# ME433_Breakout.net
KiCad netlist of a schematic drawn in EAGLE
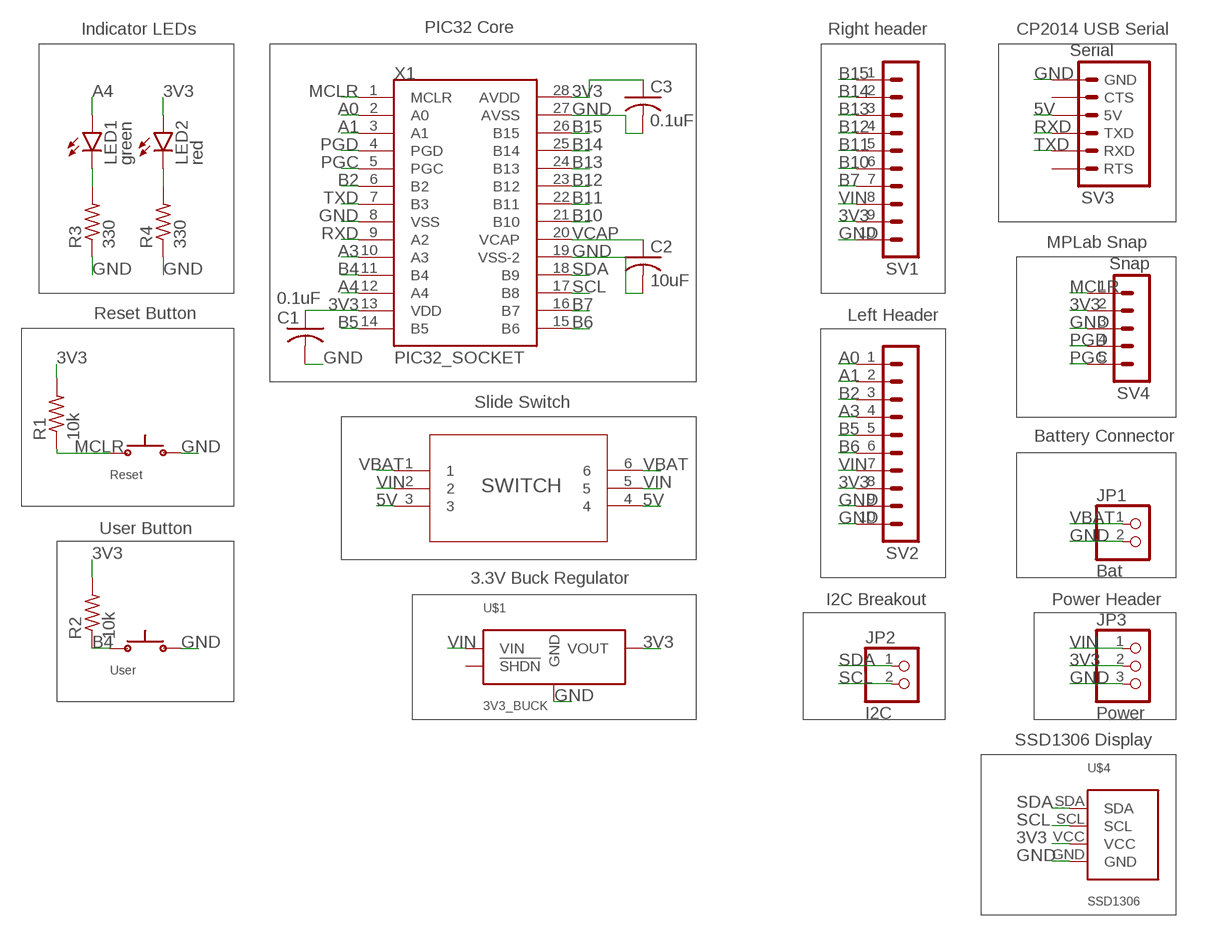
[diagram p0: schematic, sheet 1]

(export (version "E")
  (design (tool "Eeschema 10.0.6"))
  (components
    (comp (ref "C1")
      (value "0.1uF")
      (footprint "eagle-import:C025-025X050")
      (libsource (lib "eagle-import") (part "C-US025-025X050"))
    )
    (comp (ref "C2")
      (value "10uF")
      (footprint "eagle-import:C025-025X050")
      (libsource (lib "eagle-import") (part "C-US025-025X050"))
    )
    (comp (ref "C3")
      (value "0.1uF")
      (footprint "eagle-import:C025-025X050")
      (libsource (lib "eagle-import") (part "C-US025-025X050"))
    )
    (comp (ref "JP1")
      (value "Bat")
      (footprint "eagle-import:1X02")
      (libsource (lib "eagle-import") (part "PINHD-1X2"))
    )
    (comp (ref "JP2")
      (value "I2C")
      (footprint "eagle-import:1X02")
      (libsource (lib "eagle-import") (part "PINHD-1X2"))
    )
    (comp (ref "JP3")
      (value "Power")
      (footprint "eagle-import:1X03")
      (libsource (lib "eagle-import") (part "PINHD-1X3"))
    )
    (comp (ref "LED1")
      (value "green")
      (footprint "eagle-import:LED3MM")
      (libsource (lib "eagle-import") (part "LED3MM"))
    )
    (comp (ref "LED2")
      (value "red")
      (footprint "eagle-import:LED3MM")
      (libsource (lib "eagle-import") (part "LED3MM"))
    )
    (comp (ref "R1")
      (value "10k")
      (footprint "eagle-import:0207_10")
      (libsource (lib "eagle-import") (part "R-US_0207/10"))
    )
    (comp (ref "R2")
      (value "10k")
      (footprint "eagle-import:0207_10")
      (libsource (lib "eagle-import") (part "R-US_0207/10"))
    )
    (comp (ref "R3")
      (value "330")
      (footprint "eagle-import:0207_10")
      (libsource (lib "eagle-import") (part "R-US_0207/10"))
    )
    (comp (ref "R4")
      (value "330")
      (footprint "eagle-import:0207_10")
      (libsource (lib "eagle-import") (part "R-US_0207/10"))
    )
    (comp (ref "SV1")
      (value "MA10-1")
      (footprint "eagle-import:MA10-1")
      (libsource (lib "eagle-import") (part "MA10-1"))
    )
    (comp (ref "SV2")
      (value "MA10-1")
      (footprint "eagle-import:MA10-1")
      (libsource (lib "eagle-import") (part "MA10-1"))
    )
    (comp (ref "SV3")
      (value "Serial")
      (footprint "eagle-import:MA06-1")
      (libsource (lib "eagle-import") (part "CP2014_BREAKOUT"))
    )
    (comp (ref "SV4")
      (value "Snap")
      (footprint "eagle-import:MA05-1")
      (libsource (lib "eagle-import") (part "MA05-1"))
    )
    (comp (ref "U$1")
      (value "3V3_BUCK")
      (footprint "eagle-import:3V3_BUCK")
      (libsource (lib "eagle-import") (part "3V3_BUCK"))
    )
    (comp (ref "U$2")
      (value "Reset")
      (footprint "eagle-import:PUSH_BUTTON")
      (libsource (lib "eagle-import") (part "PUSH_BUTTON"))
    )
    (comp (ref "U$3")
      (value "User")
      (footprint "eagle-import:PUSH_BUTTON")
      (libsource (lib "eagle-import") (part "PUSH_BUTTON"))
    )
    (comp (ref "U$4")
      (value "SSD1306")
      (footprint "eagle-import:SSD1306")
      (libsource (lib "eagle-import") (part "SSD1306"))
    )
    (comp (ref "U1")
      (value "SWITCH")
      (footprint "eagle-import:SWITCH_011CQN")
      (fields
        (field (name "MANUFACTURER_PART_NUMBER") "JS202011CQN")
        (field (name "COPYRIGHT") "Copyright (C) 2022 Ultra Librarian. All rights reserved.")
      )
      (libsource (lib "eagle-import") (part "SWITCH"))
    )
    (comp (ref "X1")
      (value "PIC32_SOCKET")
      (footprint "eagle-import:OST_ED281DT")
      (fields
        (field (name "DIGI-KEY_PART_NUMBER") "ED3050-5-ND")
        (field (name "MF") "On Shore")
        (field (name "MP") "ED281DT")
      )
      (libsource (lib "eagle-import") (part "PIC32_SOCKET"))
    )
  )
  (nets
    (net (code "1") (name "/3V3") (class "Default")
      (node (ref "C1") (pin "1") (pinfunction "1_1") (pintype "passive"))
      (node (ref "C3") (pin "1") (pinfunction "1_1") (pintype "passive"))
      (node (ref "JP3") (pin "2") (pinfunction "2_2") (pintype "passive"))
      (node (ref "LED2") (pin "A") (pinfunction "A_A") (pintype "passive"))
      (node (ref "R1") (pin "2") (pinfunction "2_2") (pintype "passive"))
      (node (ref "R2") (pin "2") (pinfunction "2_2") (pintype "passive"))
      (node (ref "SV1") (pin "9") (pinfunction "9_9") (pintype "passive"))
      (node (ref "SV2") (pin "8") (pinfunction "8_8") (pintype "passive"))
      (node (ref "SV4") (pin "2") (pinfunction "2_2") (pintype "passive"))
      (node (ref "U$1") (pin "VOUT") (pinfunction "VOUT_VOUT") (pintype "bidirectional"))
      (node (ref "U$4") (pin "VCC") (pinfunction "VCC_VCC") (pintype "passive"))
      (node (ref "X1") (pin "13") (pinfunction "VDD_13") (pintype "passive"))
      (node (ref "X1") (pin "28") (pinfunction "AVDD_28") (pintype "passive"))
    )
    (net (code "2") (name "/5V") (class "Default")
      (node (ref "SV3") (pin "5V") (pinfunction "5V_5V") (pintype "passive"))
      (node (ref "U1") (pin "3") (pinfunction "3_3") (pintype "passive"))
      (node (ref "U1") (pin "4") (pinfunction "4_4") (pintype "passive"))
    )
    (net (code "3") (name "/A0") (class "Default")
      (node (ref "SV2") (pin "1") (pinfunction "1_1") (pintype "passive"))
      (node (ref "X1") (pin "2") (pinfunction "A0_2") (pintype "passive"))
    )
    (net (code "4") (name "/A1") (class "Default")
      (node (ref "SV2") (pin "2") (pinfunction "2_2") (pintype "passive"))
      (node (ref "X1") (pin "3") (pinfunction "A1_3") (pintype "passive"))
    )
    (net (code "5") (name "/A3") (class "Default")
      (node (ref "SV2") (pin "4") (pinfunction "4_4") (pintype "passive"))
      (node (ref "X1") (pin "10") (pinfunction "A3_10") (pintype "passive"))
    )
    (net (code "6") (name "/A4") (class "Default")
      (node (ref "LED1") (pin "A") (pinfunction "A_A") (pintype "passive"))
      (node (ref "X1") (pin "12") (pinfunction "A4_12") (pintype "passive"))
    )
    (net (code "7") (name "/B2") (class "Default")
      (node (ref "SV2") (pin "3") (pinfunction "3_3") (pintype "passive"))
      (node (ref "X1") (pin "6") (pinfunction "B2_6") (pintype "passive"))
    )
    (net (code "8") (name "/B4") (class "Default")
      (node (ref "R2") (pin "1") (pinfunction "1_1") (pintype "passive"))
      (node (ref "U$3") (pin "P$1") (pinfunction "P$1_P$1") (pintype "bidirectional"))
      (node (ref "X1") (pin "11") (pinfunction "B4_11") (pintype "passive"))
    )
    (net (code "9") (name "/B5") (class "Default")
      (node (ref "SV2") (pin "5") (pinfunction "5_5") (pintype "passive"))
      (node (ref "X1") (pin "14") (pinfunction "B5_14") (pintype "passive"))
    )
    (net (code "10") (name "/B6") (class "Default")
      (node (ref "SV2") (pin "6") (pinfunction "6_6") (pintype "passive"))
      (node (ref "X1") (pin "15") (pinfunction "B6_15") (pintype "passive"))
    )
    (net (code "11") (name "/B7") (class "Default")
      (node (ref "SV1") (pin "7") (pinfunction "7_7") (pintype "passive"))
      (node (ref "X1") (pin "16") (pinfunction "B7_16") (pintype "passive"))
    )
    (net (code "12") (name "/B10") (class "Default")
      (node (ref "SV1") (pin "6") (pinfunction "6_6") (pintype "passive"))
      (node (ref "X1") (pin "21") (pinfunction "B10_21") (pintype "passive"))
    )
    (net (code "13") (name "/B11") (class "Default")
      (node (ref "SV1") (pin "5") (pinfunction "5_5") (pintype "passive"))
      (node (ref "X1") (pin "22") (pinfunction "B11_22") (pintype "passive"))
    )
    (net (code "14") (name "/B12") (class "Default")
      (node (ref "SV1") (pin "4") (pinfunction "4_4") (pintype "passive"))
      (node (ref "X1") (pin "23") (pinfunction "B12_23") (pintype "passive"))
    )
    (net (code "15") (name "/B13") (class "Default")
      (node (ref "SV1") (pin "3") (pinfunction "3_3") (pintype "passive"))
      (node (ref "X1") (pin "24") (pinfunction "B13_24") (pintype "passive"))
    )
    (net (code "16") (name "/B14") (class "Default")
      (node (ref "SV1") (pin "2") (pinfunction "2_2") (pintype "passive"))
      (node (ref "X1") (pin "25") (pinfunction "B14_25") (pintype "passive"))
    )
    (net (code "17") (name "/B15") (class "Default")
      (node (ref "SV1") (pin "1") (pinfunction "1_1") (pintype "passive"))
      (node (ref "X1") (pin "26") (pinfunction "B15_26") (pintype "passive"))
    )
    (net (code "18") (name "/GND") (class "Default")
      (node (ref "C1") (pin "2") (pinfunction "2_2") (pintype "passive"))
      (node (ref "C2") (pin "2") (pinfunction "2_2") (pintype "passive"))
      (node (ref "C3") (pin "2") (pinfunction "2_2") (pintype "passive"))
      (node (ref "JP1") (pin "2") (pinfunction "2_2") (pintype "passive"))
      (node (ref "JP3") (pin "3") (pinfunction "3_3") (pintype "passive"))
      (node (ref "R3") (pin "1") (pinfunction "1_1") (pintype "passive"))
      (node (ref "R4") (pin "1") (pinfunction "1_1") (pintype "passive"))
      (node (ref "SV1") (pin "10") (pinfunction "10_10") (pintype "passive"))
      (node (ref "SV2") (pin "10") (pinfunction "10_10") (pintype "passive"))
      (node (ref "SV2") (pin "9") (pinfunction "9_9") (pintype "passive"))
      (node (ref "SV3") (pin "GND") (pinfunction "GND_GND") (pintype "passive"))
      (node (ref "SV4") (pin "3") (pinfunction "3_3") (pintype "passive"))
      (node (ref "U$1") (pin "GND") (pinfunction "GND_GND") (pintype "bidirectional"))
      (node (ref "U$2") (pin "P$2") (pinfunction "P$2_P$2") (pintype "bidirectional"))
      (node (ref "U$3") (pin "P$2") (pinfunction "P$2_P$2") (pintype "bidirectional"))
      (node (ref "U$4") (pin "GND") (pinfunction "GND_GND") (pintype "passive"))
      (node (ref "X1") (pin "19") (pinfunction "VSS-2_19") (pintype "passive"))
      (node (ref "X1") (pin "27") (pinfunction "AVSS_27") (pintype "passive"))
      (node (ref "X1") (pin "8") (pinfunction "VSS_8") (pintype "passive"))
    )
    (net (code "19") (name "/MCLR") (class "Default")
      (node (ref "R1") (pin "1") (pinfunction "1_1") (pintype "passive"))
      (node (ref "SV4") (pin "1") (pinfunction "1_1") (pintype "passive"))
      (node (ref "U$2") (pin "P$1") (pinfunction "P$1_P$1") (pintype "bidirectional"))
      (node (ref "X1") (pin "1") (pinfunction "MCLR_1") (pintype "passive"))
    )
    (net (code "20") (name "/PGC") (class "Default")
      (node (ref "SV4") (pin "5") (pinfunction "5_5") (pintype "passive"))
      (node (ref "X1") (pin "5") (pinfunction "PGC_5") (pintype "passive"))
    )
    (net (code "21") (name "/PGD") (class "Default")
      (node (ref "SV4") (pin "4") (pinfunction "4_4") (pintype "passive"))
      (node (ref "X1") (pin "4") (pinfunction "PGD_4") (pintype "passive"))
    )
    (net (code "22") (name "/RXD") (class "Default")
      (node (ref "SV3") (pin "TXD") (pinfunction "TXD_TXD") (pintype "passive"))
      (node (ref "X1") (pin "9") (pinfunction "A2_9") (pintype "passive"))
    )
    (net (code "23") (name "/SCL") (class "Default")
      (node (ref "JP2") (pin "2") (pinfunction "2_2") (pintype "passive"))
      (node (ref "U$4") (pin "SCL") (pinfunction "SCL_SCL") (pintype "passive"))
      (node (ref "X1") (pin "17") (pinfunction "B8_17") (pintype "passive"))
    )
    (net (code "24") (name "/SDA") (class "Default")
      (node (ref "JP2") (pin "1") (pinfunction "1_1") (pintype "passive"))
      (node (ref "U$4") (pin "SDA") (pinfunction "SDA_SDA") (pintype "passive"))
      (node (ref "X1") (pin "18") (pinfunction "B9_18") (pintype "passive"))
    )
    (net (code "25") (name "/TXD") (class "Default")
      (node (ref "SV3") (pin "RXD") (pinfunction "RXD_RXD") (pintype "passive"))
      (node (ref "X1") (pin "7") (pinfunction "B3_7") (pintype "passive"))
    )
    (net (code "26") (name "/VBAT") (class "Default")
      (node (ref "JP1") (pin "1") (pinfunction "1_1") (pintype "passive"))
      (node (ref "U1") (pin "1") (pinfunction "1_1") (pintype "passive"))
      (node (ref "U1") (pin "6") (pinfunction "6_6") (pintype "passive"))
    )
    (net (code "27") (name "/VCAP") (class "Default")
      (node (ref "C2") (pin "1") (pinfunction "1_1") (pintype "passive"))
      (node (ref "X1") (pin "20") (pinfunction "VCAP_20") (pintype "passive"))
    )
    (net (code "28") (name "/VIN") (class "Default")
      (node (ref "JP3") (pin "1") (pinfunction "1_1") (pintype "passive"))
      (node (ref "SV1") (pin "8") (pinfunction "8_8") (pintype "passive"))
      (node (ref "SV2") (pin "7") (pinfunction "7_7") (pintype "passive"))
      (node (ref "U$1") (pin "VIN") (pinfunction "VIN_VIN") (pintype "bidirectional"))
      (node (ref "U1") (pin "2") (pinfunction "2_2") (pintype "passive"))
      (node (ref "U1") (pin "5") (pinfunction "5_5") (pintype "passive"))
    )
    (net (code "29") (name "Net-(LED1-C)") (class "Default")
      (node (ref "LED1") (pin "K") (pinfunction "C_K") (pintype "passive"))
      (node (ref "R3") (pin "2") (pinfunction "2_2") (pintype "passive"))
    )
    (net (code "30") (name "Net-(LED2-C)") (class "Default")
      (node (ref "LED2") (pin "K") (pinfunction "C_K") (pintype "passive"))
      (node (ref "R4") (pin "2") (pinfunction "2_2") (pintype "passive"))
    )
    (net (code "31") (name "unconnected-(SV3-PadCTS)") (class "Default")
      (node (ref "SV3") (pin "CTS") (pinfunction "CTS_CTS") (pintype "passive"))
    )
    (net (code "32") (name "unconnected-(SV3-PadRTS)") (class "Default")
      (node (ref "SV3") (pin "RTS") (pinfunction "RTS_RTS") (pintype "passive"))
    )
    (net (code "33") (name "unconnected-(U$1-~{SHDN}-Pad!SHDN)") (class "Default")
      (node (ref "U$1") (pin "!SHDN") (pinfunction "~{SHDN}_!SHDN") (pintype "bidirectional"))
    )
  )
)
